# wifi.net
KiCad netlist of a schematic drawn in Altium Designer
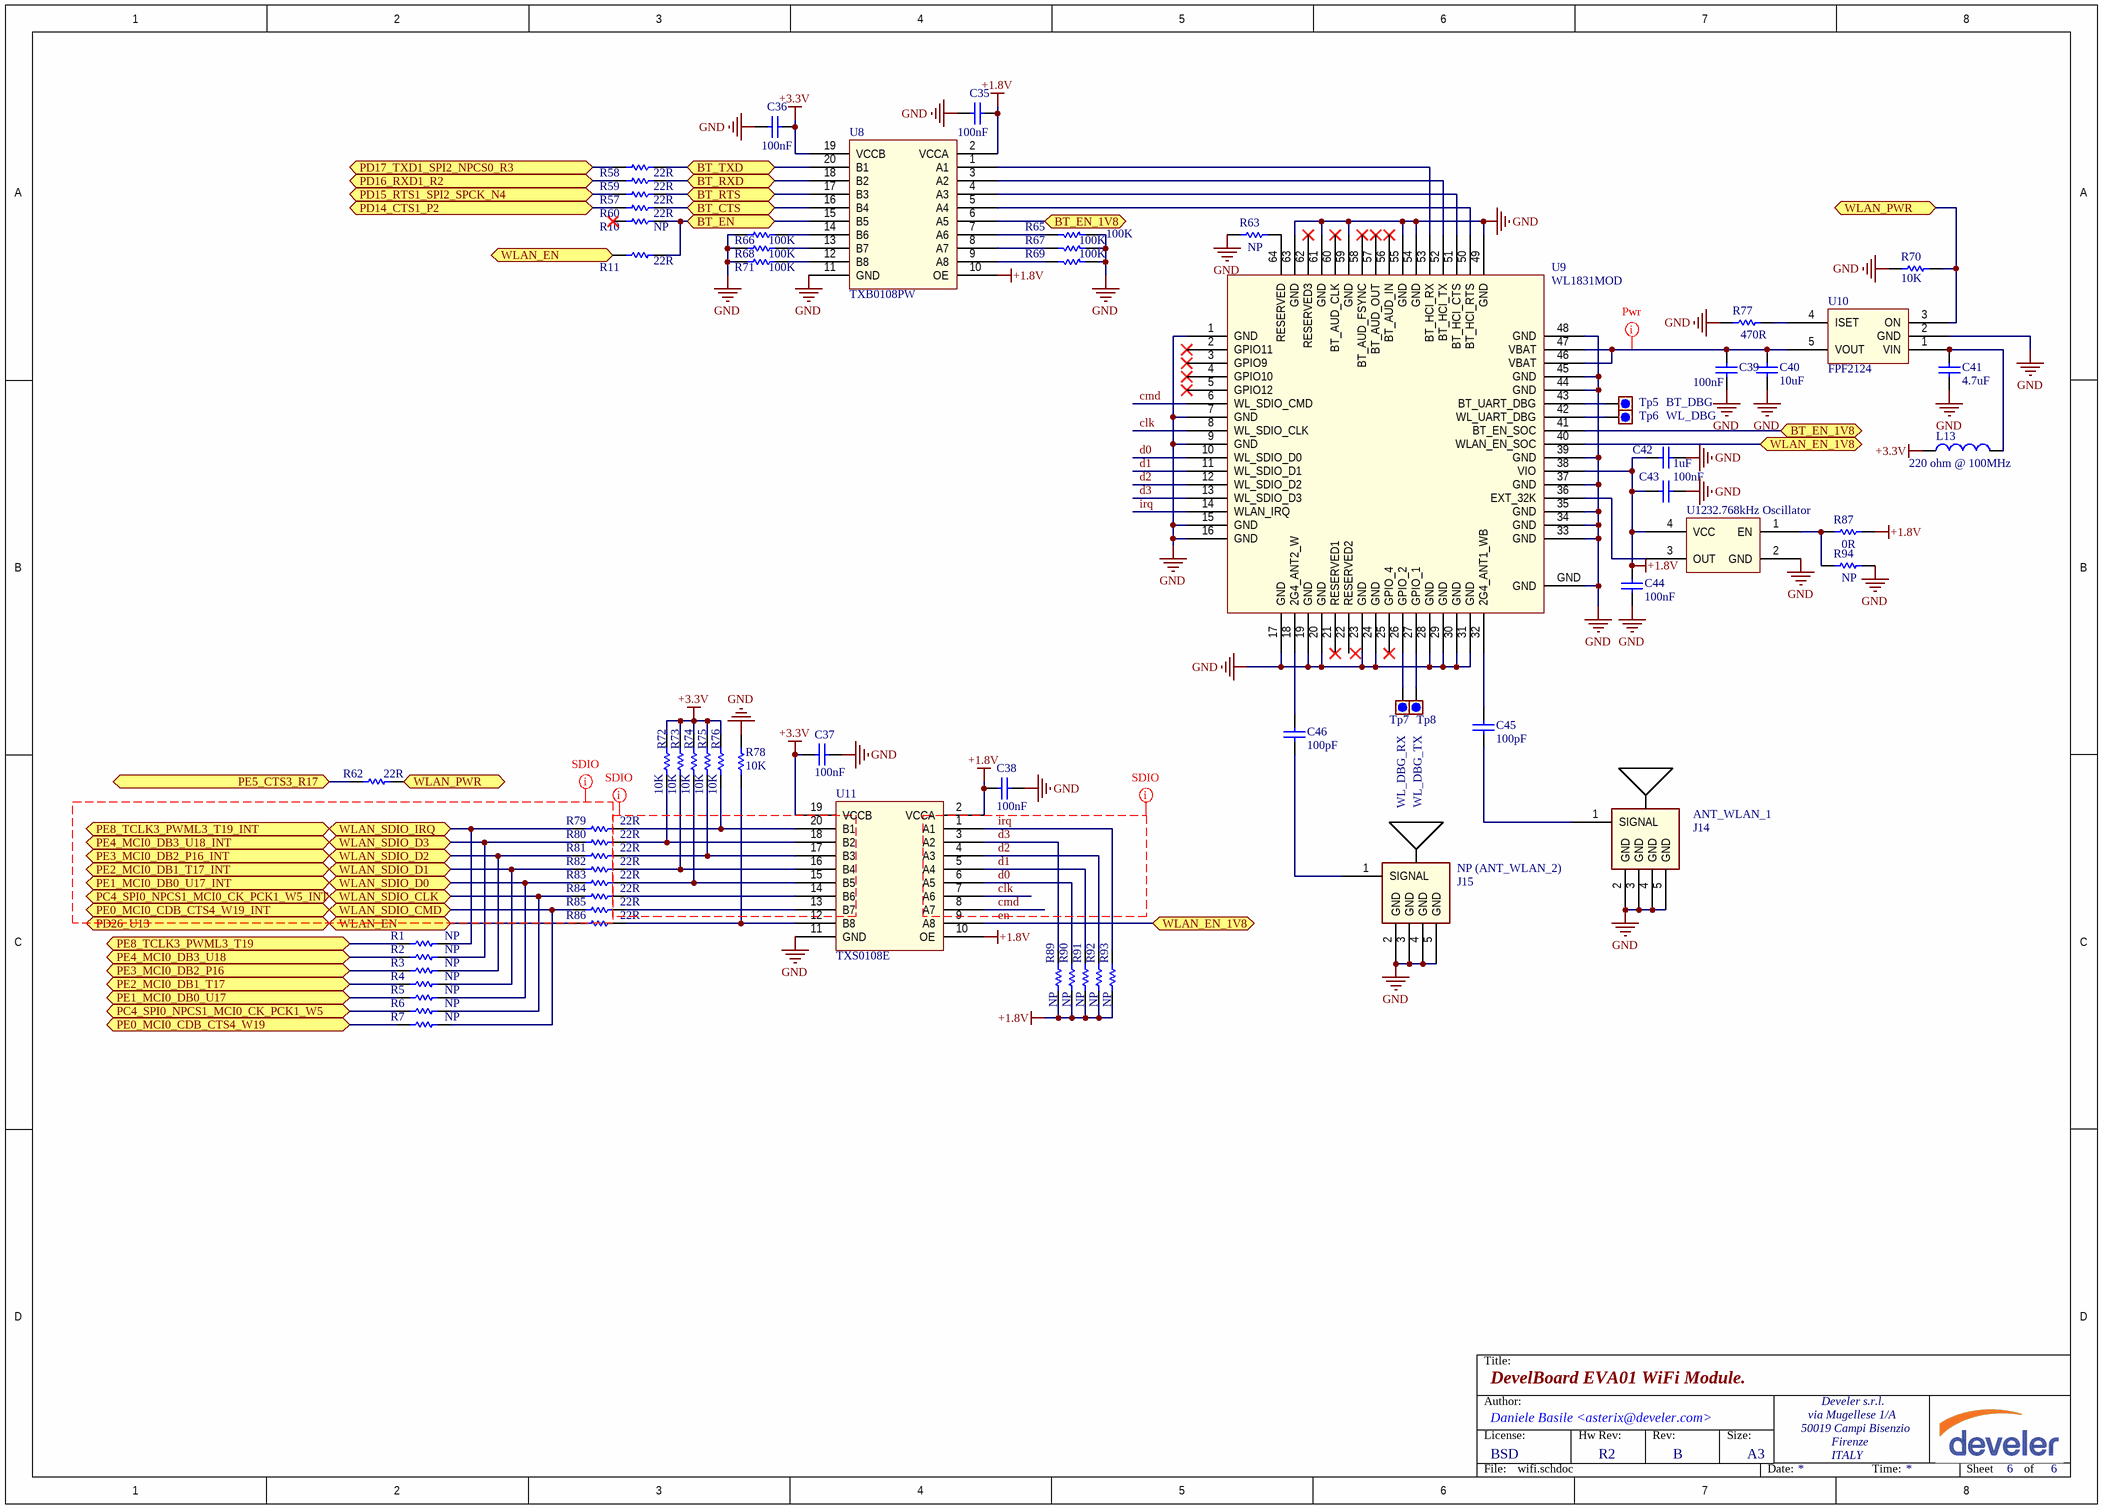
[diagram p0: wifi.schdoc]

(export (version "E")
  (design (tool "Eeschema 10.0.6"))
  (components
    (comp (ref "C35")
      (value "100nF")
      (footprint "0603_[1608]")
      (description "Ceramic X7R 50V")
      (fields (field (name "PUBLISHER") "Altium Limited"))
      (libsource (lib "DEVELER_Library") (part "Cap"))
    )
    (comp (ref "C36")
      (value "100nF")
      (footprint "0603_[1608]")
      (description "Ceramic X7R 50V")
      (fields (field (name "PUBLISHER") "Altium Limited"))
      (libsource (lib "DEVELER_Library") (part "Cap"))
    )
    (comp (ref "C37")
      (value "100nF")
      (footprint "0603_[1608]")
      (description "Ceramic X7R 50V")
      (fields (field (name "PUBLISHER") "Altium Limited"))
      (libsource (lib "DEVELER_Library") (part "Cap"))
    )
    (comp (ref "C38")
      (value "100nF")
      (footprint "0603_[1608]")
      (description "Ceramic X7R 50V")
      (fields (field (name "PUBLISHER") "Altium Limited"))
      (libsource (lib "DEVELER_Library") (part "Cap"))
    )
    (comp (ref "C39")
      (value "100nF")
      (footprint "0603_[1608]")
      (description "Ceramic X7R 50V")
      (fields (field (name "PUBLISHER") "Altium Limited"))
      (libsource (lib "DEVELER_Library") (part "Cap"))
    )
    (comp (ref "C40")
      (value "10uF")
      (footprint "1206_[3216]")
      (description "Ceramic X5R 25V")
      (fields (field (name "PUBLISHER") "Altium Limited"))
      (libsource (lib "DEVELER_Library") (part "Cap"))
    )
    (comp (ref "C41")
      (value "4.7uF")
      (footprint "0805_[2012]")
      (description "Ceramic X7R 10V")
      (fields (field (name "PUBLISHER") "Altium Limited"))
      (libsource (lib "DEVELER_Library") (part "Cap"))
    )
    (comp (ref "C42")
      (value "1uF")
      (footprint "1206_[3216]")
      (description "Ceramic X7R 50V")
      (fields (field (name "PUBLISHER") "Altium Limited"))
      (libsource (lib "DEVELER_Library") (part "Cap"))
    )
    (comp (ref "C43")
      (value "100nF")
      (footprint "0603_[1608]")
      (description "Ceramic X7R 50V")
      (fields (field (name "PUBLISHER") "Altium Limited"))
      (libsource (lib "DEVELER_Library") (part "Cap"))
    )
    (comp (ref "C44")
      (value "100nF")
      (footprint "0603_[1608]")
      (description "Ceramic X7R 50V")
      (fields (field (name "PUBLISHER") "Altium Limited"))
      (libsource (lib "DEVELER_Library") (part "Cap"))
    )
    (comp (ref "C45")
      (value "100pF")
      (footprint "0603_[1608]")
      (description "Ceramic COG 50V")
      (fields (field (name "PUBLISHER") "Altium Limited"))
      (libsource (lib "DEVELER_Library") (part "Cap"))
    )
    (comp (ref "C46")
      (value "100pF")
      (footprint "0603_[1608]")
      (description "Ceramic COG 50V")
      (fields (field (name "PUBLISHER") "Altium Limited"))
      (libsource (lib "DEVELER_Library") (part "Cap"))
    )
    (comp (ref "J14")
      (value "ANT_WLAN_1")
      (footprint "SMA_Jack_Female_5.08mm_THD")
      (description "SMA, Jack, Right angle, PCB socket, 50ohm (TE 5-1814400-1)")
      (libsource (lib "DEVELER_Library") (part "ANTENNA"))
    )
    (comp (ref "J15")
      (value "NP (ANT_WLAN_2)")
      (footprint "SMA_Jack_Female_5.08mm_THD")
      (description "SMA, Jack, Right angle, PCB socket, 50ohm (TE 5-1814400-1)")
      (libsource (lib "DEVELER_Library") (part "ANTENNA"))
    )
    (comp (ref "L13")
      (value "220 ohm @ 100MHz")
      (footprint "0805_[2012]")
      (description "Ferrite Beat (WE 742792022)")
      (libsource (lib "DEVELER_Library") (part "Inductor"))
    )
    (comp (ref "R1")
      (value "NP")
      (footprint "0603_[1608]")
      (description "Resistor")
      (fields (field (name "PUBLISHER") "Altium Limited"))
      (libsource (lib "DEVELER_Library") (part "Res1"))
    )
    (comp (ref "R2")
      (value "NP")
      (footprint "0603_[1608]")
      (description "Resistor")
      (fields (field (name "PUBLISHER") "Altium Limited"))
      (libsource (lib "DEVELER_Library") (part "Res1"))
    )
    (comp (ref "R3")
      (value "NP")
      (footprint "0603_[1608]")
      (description "Resistor")
      (fields (field (name "PUBLISHER") "Altium Limited"))
      (libsource (lib "DEVELER_Library") (part "Res1"))
    )
    (comp (ref "R4")
      (value "NP")
      (footprint "0603_[1608]")
      (description "Resistor")
      (fields (field (name "PUBLISHER") "Altium Limited"))
      (libsource (lib "DEVELER_Library") (part "Res1"))
    )
    (comp (ref "R5")
      (value "NP")
      (footprint "0603_[1608]")
      (description "Resistor")
      (fields (field (name "PUBLISHER") "Altium Limited"))
      (libsource (lib "DEVELER_Library") (part "Res1"))
    )
    (comp (ref "R6")
      (value "NP")
      (footprint "0603_[1608]")
      (description "Resistor")
      (fields (field (name "PUBLISHER") "Altium Limited"))
      (libsource (lib "DEVELER_Library") (part "Res1"))
    )
    (comp (ref "R7")
      (value "NP")
      (footprint "0603_[1608]")
      (description "Resistor")
      (fields (field (name "PUBLISHER") "Altium Limited"))
      (libsource (lib "DEVELER_Library") (part "Res1"))
    )
    (comp (ref "R10")
      (value "NP")
      (footprint "0603_[1608]")
      (description "Resistor")
      (fields (field (name "PUBLISHER") "Altium Limited"))
      (libsource (lib "DEVELER_Library") (part "Res1"))
    )
    (comp (ref "R11")
      (value "22R")
      (footprint "0603_[1608]")
      (description "Resistor")
      (fields (field (name "PUBLISHER") "Altium Limited"))
      (libsource (lib "DEVELER_Library") (part "Res1"))
    )
    (comp (ref "R57")
      (value "22R")
      (footprint "0603_[1608]")
      (description "Resistor")
      (fields (field (name "PUBLISHER") "Altium Limited"))
      (libsource (lib "DEVELER_Library") (part "Res1"))
    )
    (comp (ref "R58")
      (value "22R")
      (footprint "0603_[1608]")
      (description "Resistor")
      (fields (field (name "PUBLISHER") "Altium Limited"))
      (libsource (lib "DEVELER_Library") (part "Res1"))
    )
    (comp (ref "R59")
      (value "22R")
      (footprint "0603_[1608]")
      (description "Resistor")
      (fields (field (name "PUBLISHER") "Altium Limited"))
      (libsource (lib "DEVELER_Library") (part "Res1"))
    )
    (comp (ref "R60")
      (value "22R")
      (footprint "0603_[1608]")
      (description "Resistor")
      (fields (field (name "PUBLISHER") "Altium Limited"))
      (libsource (lib "DEVELER_Library") (part "Res1"))
    )
    (comp (ref "R62")
      (value "22R")
      (footprint "0603_[1608]")
      (description "Resistor")
      (fields (field (name "PUBLISHER") "Altium Limited"))
      (libsource (lib "DEVELER_Library") (part "Res1"))
    )
    (comp (ref "R63")
      (value "NP")
      (footprint "0603_[1608]")
      (description "Resistor")
      (fields (field (name "PUBLISHER") "Altium Limited"))
      (libsource (lib "DEVELER_Library") (part "Res1"))
    )
    (comp (ref "R65")
      (value "100K")
      (footprint "0603_[1608]")
      (description "Resistor")
      (fields (field (name "PUBLISHER") "Altium Limited"))
      (libsource (lib "DEVELER_Library") (part "Res1"))
    )
    (comp (ref "R66")
      (value "100K")
      (footprint "0603_[1608]")
      (description "Resistor")
      (fields (field (name "PUBLISHER") "Altium Limited"))
      (libsource (lib "DEVELER_Library") (part "Res1"))
    )
    (comp (ref "R67")
      (value "100K")
      (footprint "0603_[1608]")
      (description "Resistor")
      (fields (field (name "PUBLISHER") "Altium Limited"))
      (libsource (lib "DEVELER_Library") (part "Res1"))
    )
    (comp (ref "R68")
      (value "100K")
      (footprint "0603_[1608]")
      (description "Resistor")
      (fields (field (name "PUBLISHER") "Altium Limited"))
      (libsource (lib "DEVELER_Library") (part "Res1"))
    )
    (comp (ref "R69")
      (value "100K")
      (footprint "0603_[1608]")
      (description "Resistor")
      (fields (field (name "PUBLISHER") "Altium Limited"))
      (libsource (lib "DEVELER_Library") (part "Res1"))
    )
    (comp (ref "R70")
      (value "10K")
      (footprint "0603_[1608]")
      (description "Resistor")
      (fields (field (name "PUBLISHER") "Altium Limited"))
      (libsource (lib "DEVELER_Library") (part "Res1"))
    )
    (comp (ref "R71")
      (value "100K")
      (footprint "0603_[1608]")
      (description "Resistor")
      (fields (field (name "PUBLISHER") "Altium Limited"))
      (libsource (lib "DEVELER_Library") (part "Res1"))
    )
    (comp (ref "R72")
      (value "10K")
      (footprint "0603_[1608]")
      (description "Resistor")
      (fields (field (name "PUBLISHER") "Altium Limited"))
      (libsource (lib "DEVELER_Library") (part "Res1"))
    )
    (comp (ref "R73")
      (value "10K")
      (footprint "0603_[1608]")
      (description "Resistor")
      (fields (field (name "PUBLISHER") "Altium Limited"))
      (libsource (lib "DEVELER_Library") (part "Res1"))
    )
    (comp (ref "R74")
      (value "10K")
      (footprint "0603_[1608]")
      (description "Resistor")
      (fields (field (name "PUBLISHER") "Altium Limited"))
      (libsource (lib "DEVELER_Library") (part "Res1"))
    )
    (comp (ref "R75")
      (value "10K")
      (footprint "0603_[1608]")
      (description "Resistor")
      (fields (field (name "PUBLISHER") "Altium Limited"))
      (libsource (lib "DEVELER_Library") (part "Res1"))
    )
    (comp (ref "R76")
      (value "10K")
      (footprint "0603_[1608]")
      (description "Resistor")
      (fields (field (name "PUBLISHER") "Altium Limited"))
      (libsource (lib "DEVELER_Library") (part "Res1"))
    )
    (comp (ref "R77")
      (value "470R")
      (footprint "0603_[1608]")
      (description "Resistor")
      (fields (field (name "PUBLISHER") "Altium Limited"))
      (libsource (lib "DEVELER_Library") (part "Res1"))
    )
    (comp (ref "R78")
      (value "10K")
      (footprint "0603_[1608]")
      (description "Resistor")
      (fields (field (name "PUBLISHER") "Altium Limited"))
      (libsource (lib "DEVELER_Library") (part "Res1"))
    )
    (comp (ref "R79")
      (value "22R")
      (footprint "0603_[1608]")
      (description "Resistor")
      (fields (field (name "PUBLISHER") "Altium Limited"))
      (libsource (lib "DEVELER_Library") (part "Res1"))
    )
    (comp (ref "R80")
      (value "22R")
      (footprint "0603_[1608]")
      (description "Resistor")
      (fields (field (name "PUBLISHER") "Altium Limited"))
      (libsource (lib "DEVELER_Library") (part "Res1"))
    )
    (comp (ref "R81")
      (value "22R")
      (footprint "0603_[1608]")
      (description "Resistor")
      (fields (field (name "PUBLISHER") "Altium Limited"))
      (libsource (lib "DEVELER_Library") (part "Res1"))
    )
    (comp (ref "R82")
      (value "22R")
      (footprint "0603_[1608]")
      (description "Resistor")
      (fields (field (name "PUBLISHER") "Altium Limited"))
      (libsource (lib "DEVELER_Library") (part "Res1"))
    )
    (comp (ref "R83")
      (value "22R")
      (footprint "0603_[1608]")
      (description "Resistor")
      (fields (field (name "PUBLISHER") "Altium Limited"))
      (libsource (lib "DEVELER_Library") (part "Res1"))
    )
    (comp (ref "R84")
      (value "22R")
      (footprint "0603_[1608]")
      (description "Resistor")
      (fields (field (name "PUBLISHER") "Altium Limited"))
      (libsource (lib "DEVELER_Library") (part "Res1"))
    )
    (comp (ref "R85")
      (value "22R")
      (footprint "0603_[1608]")
      (description "Resistor")
      (fields (field (name "PUBLISHER") "Altium Limited"))
      (libsource (lib "DEVELER_Library") (part "Res1"))
    )
    (comp (ref "R86")
      (value "22R")
      (footprint "0603_[1608]")
      (description "Resistor")
      (fields (field (name "PUBLISHER") "Altium Limited"))
      (libsource (lib "DEVELER_Library") (part "Res1"))
    )
    (comp (ref "R87")
      (value "0R")
      (footprint "0603_[1608]")
      (description "Resistor")
      (fields (field (name "PUBLISHER") "Altium Limited"))
      (libsource (lib "DEVELER_Library") (part "Res1"))
    )
    (comp (ref "R89")
      (value "NP")
      (footprint "0603_[1608]")
      (description "Resistor")
      (fields (field (name "PUBLISHER") "Altium Limited"))
      (libsource (lib "DEVELER_Library") (part "Res1"))
    )
    (comp (ref "R90")
      (value "NP")
      (footprint "0603_[1608]")
      (description "Resistor")
      (fields (field (name "PUBLISHER") "Altium Limited"))
      (libsource (lib "DEVELER_Library") (part "Res1"))
    )
    (comp (ref "R91")
      (value "NP")
      (footprint "0603_[1608]")
      (description "Resistor")
      (fields (field (name "PUBLISHER") "Altium Limited"))
      (libsource (lib "DEVELER_Library") (part "Res1"))
    )
    (comp (ref "R92")
      (value "NP")
      (footprint "0603_[1608]")
      (description "Resistor")
      (fields (field (name "PUBLISHER") "Altium Limited"))
      (libsource (lib "DEVELER_Library") (part "Res1"))
    )
    (comp (ref "R93")
      (value "NP")
      (footprint "0603_[1608]")
      (description "Resistor")
      (fields (field (name "PUBLISHER") "Altium Limited"))
      (libsource (lib "DEVELER_Library") (part "Res1"))
    )
    (comp (ref "R94")
      (value "NP")
      (footprint "0603_[1608]")
      (description "Resistor")
      (fields (field (name "PUBLISHER") "Altium Limited"))
      (libsource (lib "DEVELER_Library") (part "Res1"))
    )
    (comp (ref "Tp5")
      (value "BT_DBG")
      (footprint "TEST_POINT_SMD_D1MM")
      (description "Test point")
      (libsource (lib "DEVELER_Library") (part "Test_point"))
    )
    (comp (ref "Tp6")
      (value "WL_DBG")
      (footprint "TEST_POINT_SMD_D1MM")
      (description "Test point")
      (libsource (lib "DEVELER_Library") (part "Test_point"))
    )
    (comp (ref "Tp7")
      (value "WL_DBG_RX")
      (footprint "TEST_POINT_SMD_D1MM")
      (description "Test point")
      (libsource (lib "") (part "Test_point_1"))
    )
    (comp (ref "Tp8")
      (value "WL_DBG_TX")
      (footprint "TEST_POINT_SMD_D1MM")
      (description "Test point")
      (libsource (lib "") (part "Test_point_1"))
    )
    (comp (ref "U8")
      (value "TXB0108PW")
      (footprint "TSOP65P640X120-20L")
      (description "8-bit bidirectional level translator")
      (libsource (lib "DEVELER_Library") (part "TXB0108PW"))
    )
    (comp (ref "U9")
      (value "WL1831MOD")
      (footprint "WL18XX_E-13.4X13.3-N100_0.75")
      (description "Wifi & Bluethoot module")
      (libsource (lib "DEVELER_Library") (part "WL1831MOD"))
    )
    (comp (ref "U10")
      (value "FPF2124")
      (footprint "SOT-23-5")
      (description "Power Load Switch")
      (libsource (lib "DEVELER_Library") (part "FPF2124"))
    )
    (comp (ref "U11")
      (value "TXS0108E")
      (footprint "TSOP65P640X120-20L")
      (description "8-bit bidirectional level translator")
      (libsource (lib "DEVELER_Library") (part "TXB0108PW"))
    )
    (comp (ref "U12")
      (value "32.768kHz Oscillator")
      (footprint "CRYSTAL_3.2X1.5MM_4P_SMD")
      (description "32.768kHz Oscillator (EPSON  X1B0002110001 SG-3030CM)")
      (libsource (lib "DEVELER_Library") (part "Si501/2/3_32768Hz"))
    )
  )
  (nets
    (net (code "1") (name "+1.8V") (class "Default")
      (node (ref "C35") (pin "2") (pinfunction "2_2") (pintype "passive"))
      (node (ref "C38") (pin "2") (pinfunction "2_2") (pintype "passive"))
      (node (ref "C42") (pin "2") (pinfunction "2_2") (pintype "passive"))
      (node (ref "C43") (pin "2") (pinfunction "2_2") (pintype "passive"))
      (node (ref "C44") (pin "2") (pinfunction "2_2") (pintype "passive"))
      (node (ref "R87") (pin "1") (pinfunction "1_1") (pintype "passive"))
      (node (ref "R89") (pin "1") (pinfunction "1_1") (pintype "passive"))
      (node (ref "R90") (pin "1") (pinfunction "1_1") (pintype "passive"))
      (node (ref "R91") (pin "1") (pinfunction "1_1") (pintype "passive"))
      (node (ref "R92") (pin "1") (pinfunction "1_1") (pintype "passive"))
      (node (ref "R93") (pin "1") (pinfunction "1_1") (pintype "passive"))
      (node (ref "U11") (pin "10") (pinfunction "OE_10") (pintype "passive"))
      (node (ref "U11") (pin "2") (pinfunction "VCCA_2") (pintype "passive"))
      (node (ref "U12") (pin "4") (pinfunction "VCC_4") (pintype "passive"))
      (node (ref "U8") (pin "10") (pinfunction "OE_10") (pintype "passive"))
      (node (ref "U8") (pin "2") (pinfunction "VCCA_2") (pintype "passive"))
      (node (ref "U9") (pin "38") (pinfunction "VIO_38") (pintype "passive"))
    )
    (net (code "2") (name "+3.3V") (class "Default")
      (node (ref "C36") (pin "2") (pinfunction "2_2") (pintype "passive"))
      (node (ref "C37") (pin "2") (pinfunction "2_2") (pintype "passive"))
      (node (ref "L13") (pin "2") (pinfunction "2_2") (pintype "passive"))
      (node (ref "R72") (pin "1") (pinfunction "1_1") (pintype "passive"))
      (node (ref "R73") (pin "1") (pinfunction "1_1") (pintype "passive"))
      (node (ref "R74") (pin "1") (pinfunction "1_1") (pintype "passive"))
      (node (ref "R75") (pin "1") (pinfunction "1_1") (pintype "passive"))
      (node (ref "R76") (pin "1") (pinfunction "1_1") (pintype "passive"))
      (node (ref "U11") (pin "19") (pinfunction "VCCB_19") (pintype "passive"))
      (node (ref "U8") (pin "19") (pinfunction "VCCB_19") (pintype "passive"))
    )
    (net (code "3") (name "/BT_CTS") (class "Default")
      (node (ref "R60") (pin "2") (pinfunction "2_2") (pintype "passive"))
      (node (ref "U8") (pin "16") (pinfunction "B4_16") (pintype "passive"))
    )
    (net (code "4") (name "/BT_EN") (class "Default")
      (node (ref "R10") (pin "2") (pinfunction "2_2") (pintype "passive"))
      (node (ref "R11") (pin "2") (pinfunction "2_2") (pintype "passive"))
      (node (ref "U8") (pin "15") (pinfunction "B5_15") (pintype "passive"))
    )
    (net (code "5") (name "/BT_EN_1V8") (class "Default")
      (node (ref "U8") (pin "6") (pinfunction "A5_6") (pintype "passive"))
      (node (ref "U9") (pin "41") (pinfunction "BT_EN_SOC_41") (pintype "passive"))
    )
    (net (code "6") (name "/BT_RTS") (class "Default")
      (node (ref "R57") (pin "2") (pinfunction "2_2") (pintype "passive"))
      (node (ref "U8") (pin "17") (pinfunction "B3_17") (pintype "passive"))
    )
    (net (code "7") (name "/BT_RXD") (class "Default")
      (node (ref "R59") (pin "2") (pinfunction "2_2") (pintype "passive"))
      (node (ref "U8") (pin "18") (pinfunction "B2_18") (pintype "passive"))
    )
    (net (code "8") (name "/BT_TXD") (class "Default")
      (node (ref "R58") (pin "2") (pinfunction "2_2") (pintype "passive"))
      (node (ref "U8") (pin "20") (pinfunction "B1_20") (pintype "passive"))
    )
    (net (code "9") (name "/PC4_SPI0_NPCS1_MCI0_CK_PCK1_W5") (class "Default")
      (node (ref "R6") (pin "2") (pinfunction "2_2") (pintype "passive"))
    )
    (net (code "11") (name "/PD14_CTS1_P2") (class "Default")
      (node (ref "R60") (pin "1") (pinfunction "1_1") (pintype "passive"))
    )
    (net (code "12") (name "/PD15_RTS1_SPI2_SPCK_N4") (class "Default")
      (node (ref "R57") (pin "1") (pinfunction "1_1") (pintype "passive"))
    )
    (net (code "13") (name "/PD16_RXD1_R2") (class "Default")
      (node (ref "R59") (pin "1") (pinfunction "1_1") (pintype "passive"))
    )
    (net (code "14") (name "/PD17_TXD1_SPI2_NPCS0_R3") (class "Default")
      (node (ref "R58") (pin "1") (pinfunction "1_1") (pintype "passive"))
    )
    (net (code "16") (name "/PE0_MCI0_CDB_CTS4_W19") (class "Default")
      (node (ref "R7") (pin "2") (pinfunction "2_2") (pintype "passive"))
    )
    (net (code "18") (name "/PE1_MCI0_DB0_U17") (class "Default")
      (node (ref "R5") (pin "2") (pinfunction "2_2") (pintype "passive"))
    )
    (net (code "20") (name "/PE2_MCI0_DB1_T17") (class "Default")
      (node (ref "R4") (pin "2") (pinfunction "2_2") (pintype "passive"))
    )
    (net (code "22") (name "/PE3_MCI0_DB2_P16") (class "Default")
      (node (ref "R3") (pin "2") (pinfunction "2_2") (pintype "passive"))
    )
    (net (code "24") (name "/PE4_MCI0_DB3_U18") (class "Default")
      (node (ref "R2") (pin "2") (pinfunction "2_2") (pintype "passive"))
    )
    (net (code "26") (name "/PE5_CTS3_R17") (class "Default")
      (node (ref "R62") (pin "1") (pinfunction "1_1") (pintype "passive"))
    )
    (net (code "27") (name "/PE8_TCLK3_PWML3_T19") (class "Default")
      (node (ref "R1") (pin "2") (pinfunction "2_2") (pintype "passive"))
    )
    (net (code "29") (name "/WLAN_EN") (class "Default")
      (node (ref "R11") (pin "1") (pinfunction "1_1") (pintype "passive"))
      (node (ref "R86") (pin "2") (pinfunction "2_2") (pintype "passive"))
    )
    (net (code "30") (name "/WLAN_PWR") (class "Default")
      (node (ref "R62") (pin "2") (pinfunction "2_2") (pintype "passive"))
      (node (ref "R70") (pin "2") (pinfunction "2_2") (pintype "passive"))
      (node (ref "U10") (pin "3") (pinfunction "ON_3") (pintype "passive"))
    )
    (net (code "31") (name "/WLAN_SDIO_CLK") (class "Default")
      (node (ref "R6") (pin "1") (pinfunction "1_1") (pintype "passive"))
      (node (ref "R84") (pin "2") (pinfunction "2_2") (pintype "passive"))
    )
    (net (code "32") (name "/WLAN_SDIO_CMD") (class "Default")
      (node (ref "R7") (pin "1") (pinfunction "1_1") (pintype "passive"))
      (node (ref "R85") (pin "2") (pinfunction "2_2") (pintype "passive"))
    )
    (net (code "33") (name "/WLAN_SDIO_D0") (class "Default")
      (node (ref "R5") (pin "1") (pinfunction "1_1") (pintype "passive"))
      (node (ref "R83") (pin "2") (pinfunction "2_2") (pintype "passive"))
    )
    (net (code "34") (name "/WLAN_SDIO_D1") (class "Default")
      (node (ref "R4") (pin "1") (pinfunction "1_1") (pintype "passive"))
      (node (ref "R82") (pin "2") (pinfunction "2_2") (pintype "passive"))
    )
    (net (code "35") (name "/WLAN_SDIO_D2") (class "Default")
      (node (ref "R3") (pin "1") (pinfunction "1_1") (pintype "passive"))
      (node (ref "R81") (pin "2") (pinfunction "2_2") (pintype "passive"))
    )
    (net (code "36") (name "/WLAN_SDIO_D3") (class "Default")
      (node (ref "R2") (pin "1") (pinfunction "1_1") (pintype "passive"))
      (node (ref "R80") (pin "2") (pinfunction "2_2") (pintype "passive"))
    )
    (net (code "37") (name "/WLAN_SDIO_IRQ") (class "Default")
      (node (ref "R1") (pin "1") (pinfunction "1_1") (pintype "passive"))
      (node (ref "R79") (pin "2") (pinfunction "2_2") (pintype "passive"))
    )
    (net (code "38") (name "/clk") (class "Default")
      (node (ref "U11") (pin "7") (pinfunction "A6_7") (pintype "passive"))
      (node (ref "U9") (pin "8") (pinfunction "WL_SDIO_CLK_8") (pintype "passive"))
    )
    (net (code "39") (name "/cmd") (class "Default")
      (node (ref "U11") (pin "8") (pinfunction "A7_8") (pintype "passive"))
      (node (ref "U9") (pin "6") (pinfunction "WL_SDIO_CMD_6") (pintype "passive"))
    )
    (net (code "40") (name "/d0") (class "Default")
      (node (ref "R90") (pin "2") (pinfunction "2_2") (pintype "passive"))
      (node (ref "U11") (pin "6") (pinfunction "A5_6") (pintype "passive"))
      (node (ref "U9") (pin "10") (pinfunction "WL_SDIO_D0_10") (pintype "passive"))
    )
    (net (code "41") (name "/d1") (class "Default")
      (node (ref "R91") (pin "2") (pinfunction "2_2") (pintype "passive"))
      (node (ref "U11") (pin "5") (pinfunction "A4_5") (pintype "passive"))
      (node (ref "U9") (pin "11") (pinfunction "WL_SDIO_D1_11") (pintype "passive"))
    )
    (net (code "42") (name "/d2") (class "Default")
      (node (ref "R92") (pin "2") (pinfunction "2_2") (pintype "passive"))
      (node (ref "U11") (pin "4") (pinfunction "A3_4") (pintype "passive"))
      (node (ref "U9") (pin "12") (pinfunction "WL_SDIO_D2_12") (pintype "passive"))
    )
    (net (code "43") (name "/d3") (class "Default")
      (node (ref "R89") (pin "2") (pinfunction "2_2") (pintype "passive"))
      (node (ref "U11") (pin "3") (pinfunction "A2_3") (pintype "passive"))
      (node (ref "U9") (pin "13") (pinfunction "WL_SDIO_D3_13") (pintype "passive"))
    )
    (net (code "44") (name "/en") (class "Default")
      (node (ref "U11") (pin "9") (pinfunction "A8_9") (pintype "passive"))
      (node (ref "U9") (pin "40") (pinfunction "WLAN_EN_SOC_40") (pintype "passive"))
    )
    (net (code "45") (name "/irq") (class "Default")
      (node (ref "R93") (pin "2") (pinfunction "2_2") (pintype "passive"))
      (node (ref "U11") (pin "1") (pinfunction "A1_1") (pintype "passive"))
      (node (ref "U9") (pin "14") (pinfunction "WLAN_IRQ_14") (pintype "passive"))
    )
    (net (code "46") (name "GND") (class "Default")
      (node (ref "C35") (pin "1") (pinfunction "1_1") (pintype "passive"))
      (node (ref "C36") (pin "1") (pinfunction "1_1") (pintype "passive"))
      (node (ref "C37") (pin "1") (pinfunction "1_1") (pintype "passive"))
      (node (ref "C38") (pin "1") (pinfunction "1_1") (pintype "passive"))
      (node (ref "C39") (pin "1") (pinfunction "1_1") (pintype "passive"))
      (node (ref "C40") (pin "1") (pinfunction "1_1") (pintype "passive"))
      (node (ref "C41") (pin "1") (pinfunction "1_1") (pintype "passive"))
      (node (ref "C42") (pin "1") (pinfunction "1_1") (pintype "passive"))
      (node (ref "C43") (pin "1") (pinfunction "1_1") (pintype "passive"))
      (node (ref "C44") (pin "1") (pinfunction "1_1") (pintype "passive"))
      (node (ref "J14") (pin "2") (pinfunction "GND_2") (pintype "passive"))
      (node (ref "J14") (pin "3") (pinfunction "GND_3") (pintype "passive"))
      (node (ref "J14") (pin "4") (pinfunction "GND_4") (pintype "passive"))
      (node (ref "J14") (pin "5") (pinfunction "GND_5") (pintype "passive"))
      (node (ref "J15") (pin "2") (pinfunction "GND_2") (pintype "passive"))
      (node (ref "J15") (pin "3") (pinfunction "GND_3") (pintype "passive"))
      (node (ref "J15") (pin "4") (pinfunction "GND_4") (pintype "passive"))
      (node (ref "J15") (pin "5") (pinfunction "GND_5") (pintype "passive"))
      (node (ref "R63") (pin "2") (pinfunction "2_2") (pintype "passive"))
      (node (ref "R65") (pin "2") (pinfunction "2_2") (pintype "passive"))
      (node (ref "R66") (pin "2") (pinfunction "2_2") (pintype "passive"))
      (node (ref "R67") (pin "2") (pinfunction "2_2") (pintype "passive"))
      (node (ref "R68") (pin "2") (pinfunction "2_2") (pintype "passive"))
      (node (ref "R69") (pin "2") (pinfunction "2_2") (pintype "passive"))
      (node (ref "R70") (pin "1") (pinfunction "1_1") (pintype "passive"))
      (node (ref "R71") (pin "2") (pinfunction "2_2") (pintype "passive"))
      (node (ref "R77") (pin "2") (pinfunction "2_2") (pintype "passive"))
      (node (ref "R78") (pin "1") (pinfunction "1_1") (pintype "passive"))
      (node (ref "R94") (pin "1") (pinfunction "1_1") (pintype "passive"))
      (node (ref "U10") (pin "2") (pinfunction "GND_2") (pintype "passive"))
      (node (ref "U11") (pin "11") (pinfunction "GND_11") (pintype "passive"))
      (node (ref "U12") (pin "2") (pinfunction "GND_2") (pintype "passive"))
      (node (ref "U8") (pin "11") (pinfunction "GND_11") (pintype "passive"))
      (node (ref "U9") (pin "1") (pinfunction "GND_1") (pintype "passive"))
      (node (ref "U9") (pin "15") (pinfunction "GND_15") (pintype "passive"))
      (node (ref "U9") (pin "16") (pinfunction "GND_16") (pintype "passive"))
      (node (ref "U9") (pin "17") (pinfunction "GND_17") (pintype "passive"))
      (node (ref "U9") (pin "19") (pinfunction "GND_19") (pintype "passive"))
      (node (ref "U9") (pin "20") (pinfunction "GND_20") (pintype "passive"))
      (node (ref "U9") (pin "23") (pinfunction "GND_23") (pintype "passive"))
      (node (ref "U9") (pin "24") (pinfunction "GND_24") (pintype "passive"))
      (node (ref "U9") (pin "28") (pinfunction "GND_28") (pintype "passive"))
      (node (ref "U9") (pin "29") (pinfunction "GND_29") (pintype "passive"))
      (node (ref "U9") (pin "30") (pinfunction "GND_30") (pintype "passive"))
      (node (ref "U9") (pin "31") (pinfunction "GND_31") (pintype "passive"))
      (node (ref "U9") (pin "33") (pinfunction "GND_33") (pintype "passive"))
      (node (ref "U9") (pin "34") (pinfunction "GND_34") (pintype "passive"))
      (node (ref "U9") (pin "35") (pinfunction "GND_35") (pintype "passive"))
      (node (ref "U9") (pin "37") (pinfunction "GND_37") (pintype "passive"))
      (node (ref "U9") (pin "39") (pinfunction "GND_39") (pintype "passive"))
      (node (ref "U9") (pin "44") (pinfunction "GND_44") (pintype "passive"))
      (node (ref "U9") (pin "45") (pinfunction "GND_45") (pintype "passive"))
      (node (ref "U9") (pin "48") (pinfunction "GND_48") (pintype "passive"))
      (node (ref "U9") (pin "49") (pinfunction "GND_49") (pintype "passive"))
      (node (ref "U9") (pin "54") (pinfunction "GND_54") (pintype "passive"))
      (node (ref "U9") (pin "55") (pinfunction "GND_55") (pintype "passive"))
      (node (ref "U9") (pin "59") (pinfunction "GND_59") (pintype "passive"))
      (node (ref "U9") (pin "61") (pinfunction "GND_61") (pintype "passive"))
      (node (ref "U9") (pin "63") (pinfunction "GND_63") (pintype "passive"))
      (node (ref "U9") (pin "7") (pinfunction "GND_7") (pintype "passive"))
      (node (ref "U9") (pin "9") (pinfunction "GND_9") (pintype "passive"))
      (node (ref "U9") (pin "GND") (pinfunction "GND_GND") (pintype "passive"))
    )
    (net (code "47") (name "Net-(J14-SIGNAL)") (class "Default")
      (node (ref "C45") (pin "2") (pinfunction "2_2") (pintype "passive"))
      (node (ref "J14") (pin "1") (pinfunction "SIGNAL_1") (pintype "passive"))
    )
    (net (code "48") (name "Net-(J15-SIGNAL)") (class "Default")
      (node (ref "C46") (pin "2") (pinfunction "2_2") (pintype "passive"))
      (node (ref "J15") (pin "1") (pinfunction "SIGNAL_1") (pintype "passive"))
    )
    (net (code "49") (name "Net-(U8-A1)") (class "Default")
      (node (ref "U8") (pin "1") (pinfunction "A1_1") (pintype "passive"))
      (node (ref "U9") (pin "53") (pinfunction "BT_HCI_RX_53") (pintype "passive"))
    )
    (net (code "50") (name "Net-(U8-A2)") (class "Default")
      (node (ref "U8") (pin "3") (pinfunction "A2_3") (pintype "passive"))
      (node (ref "U9") (pin "52") (pinfunction "BT_HCI_TX_52") (pintype "passive"))
    )
    (net (code "51") (name "Net-(U8-A3)") (class "Default")
      (node (ref "U8") (pin "4") (pinfunction "A3_4") (pintype "passive"))
      (node (ref "U9") (pin "51") (pinfunction "BT_HCI_CTS_51") (pintype "passive"))
    )
    (net (code "52") (name "Net-(U8-A4)") (class "Default")
      (node (ref "U8") (pin "5") (pinfunction "A4_5") (pintype "passive"))
      (node (ref "U9") (pin "50") (pinfunction "BT_HCI_RTS_50") (pintype "passive"))
    )
    (net (code "53") (name "Net-(U8-A6)") (class "Default")
      (node (ref "R65") (pin "1") (pinfunction "1_1") (pintype "passive"))
      (node (ref "U8") (pin "7") (pinfunction "A6_7") (pintype "passive"))
    )
    (net (code "54") (name "Net-(U8-A7)") (class "Default")
      (node (ref "R67") (pin "1") (pinfunction "1_1") (pintype "passive"))
      (node (ref "U8") (pin "8") (pinfunction "A7_8") (pintype "passive"))
    )
    (net (code "55") (name "Net-(U8-A8)") (class "Default")
      (node (ref "R69") (pin "1") (pinfunction "1_1") (pintype "passive"))
      (node (ref "U8") (pin "9") (pinfunction "A8_9") (pintype "passive"))
    )
    (net (code "56") (name "Net-(U8-B6)") (class "Default")
      (node (ref "R66") (pin "1") (pinfunction "1_1") (pintype "passive"))
      (node (ref "U8") (pin "14") (pinfunction "B6_14") (pintype "passive"))
    )
    (net (code "57") (name "Net-(U8-B7)") (class "Default")
      (node (ref "R68") (pin "1") (pinfunction "1_1") (pintype "passive"))
      (node (ref "U8") (pin "13") (pinfunction "B7_13") (pintype "passive"))
    )
    (net (code "58") (name "Net-(U8-B8)") (class "Default")
      (node (ref "R71") (pin "1") (pinfunction "1_1") (pintype "passive"))
      (node (ref "U8") (pin "12") (pinfunction "B8_12") (pintype "passive"))
    )
    (net (code "59") (name "Net-(U9-2G4_ANT1_WB)") (class "Default")
      (node (ref "C45") (pin "1") (pinfunction "1_1") (pintype "passive"))
      (node (ref "U9") (pin "32") (pinfunction "2G4_ANT1_WB_32") (pintype "passive"))
    )
    (net (code "60") (name "Net-(U9-2G4_ANT2_W)") (class "Default")
      (node (ref "C46") (pin "1") (pinfunction "1_1") (pintype "passive"))
      (node (ref "U9") (pin "18") (pinfunction "2G4_ANT2_W_18") (pintype "passive"))
    )
    (net (code "61") (name "Net-(U9-BT_UART_DBG)") (class "Default")
      (node (ref "Tp5") (pin "1") (pinfunction "1_1") (pintype "passive"))
      (node (ref "U9") (pin "43") (pinfunction "BT_UART_DBG_43") (pintype "passive"))
    )
    (net (code "62") (name "Net-(U9-GPIO_1)") (class "Default")
      (node (ref "Tp8") (pin "1") (pinfunction "1_1") (pintype "passive"))
      (node (ref "U9") (pin "27") (pinfunction "GPIO_1_27") (pintype "passive"))
    )
    (net (code "63") (name "Net-(U9-GPIO_2)") (class "Default")
      (node (ref "Tp7") (pin "1") (pinfunction "1_1") (pintype "passive"))
      (node (ref "U9") (pin "26") (pinfunction "GPIO_2_26") (pintype "passive"))
    )
    (net (code "64") (name "Net-(U9-RESERVED)") (class "Default")
      (node (ref "R63") (pin "1") (pinfunction "1_1") (pintype "passive"))
      (node (ref "U9") (pin "64") (pinfunction "RESERVED_64") (pintype "passive"))
    )
    (net (code "65") (name "Net-(U9-WL_UART_DBG)") (class "Default")
      (node (ref "Tp6") (pin "1") (pinfunction "1_1") (pintype "passive"))
      (node (ref "U9") (pin "42") (pinfunction "WL_UART_DBG_42") (pintype "passive"))
    )
    (net (code "66") (name "Net-(U10-ISET)") (class "Default")
      (node (ref "R77") (pin "1") (pinfunction "1_1") (pintype "passive"))
      (node (ref "U10") (pin "4") (pinfunction "ISET_4") (pintype "passive"))
    )
    (net (code "67") (name "Net-(U10-VIN)") (class "Default")
      (node (ref "C41") (pin "2") (pinfunction "2_2") (pintype "passive"))
      (node (ref "L13") (pin "1") (pinfunction "1_1") (pintype "passive"))
      (node (ref "U10") (pin "1") (pinfunction "VIN_1") (pintype "passive"))
    )
    (net (code "68") (name "Net-(U10-VOUT)") (class "Default")
      (node (ref "C39") (pin "2") (pinfunction "2_2") (pintype "passive"))
      (node (ref "C40") (pin "2") (pinfunction "2_2") (pintype "passive"))
      (node (ref "U10") (pin "5") (pinfunction "VOUT_5") (pintype "passive"))
      (node (ref "U9") (pin "46") (pinfunction "VBAT_46") (pintype "passive"))
      (node (ref "U9") (pin "47") (pinfunction "VBAT_47") (pintype "passive"))
    )
    (net (code "69") (name "Net-(U11-B1)") (class "Default")
      (node (ref "R76") (pin "2") (pinfunction "2_2") (pintype "passive"))
      (node (ref "R79") (pin "1") (pinfunction "1_1") (pintype "passive"))
      (node (ref "U11") (pin "20") (pinfunction "B1_20") (pintype "passive"))
    )
    (net (code "70") (name "Net-(U11-B2)") (class "Default")
      (node (ref "R72") (pin "2") (pinfunction "2_2") (pintype "passive"))
      (node (ref "R80") (pin "1") (pinfunction "1_1") (pintype "passive"))
      (node (ref "U11") (pin "18") (pinfunction "B2_18") (pintype "passive"))
    )
    (net (code "71") (name "Net-(U11-B3)") (class "Default")
      (node (ref "R75") (pin "2") (pinfunction "2_2") (pintype "passive"))
      (node (ref "R81") (pin "1") (pinfunction "1_1") (pintype "passive"))
      (node (ref "U11") (pin "17") (pinfunction "B3_17") (pintype "passive"))
    )
    (net (code "72") (name "Net-(U11-B4)") (class "Default")
      (node (ref "R73") (pin "2") (pinfunction "2_2") (pintype "passive"))
      (node (ref "R82") (pin "1") (pinfunction "1_1") (pintype "passive"))
      (node (ref "U11") (pin "16") (pinfunction "B4_16") (pintype "passive"))
    )
    (net (code "73") (name "Net-(U11-B5)") (class "Default")
      (node (ref "R74") (pin "2") (pinfunction "2_2") (pintype "passive"))
      (node (ref "R83") (pin "1") (pinfunction "1_1") (pintype "passive"))
      (node (ref "U11") (pin "15") (pinfunction "B5_15") (pintype "passive"))
    )
    (net (code "74") (name "Net-(U11-B6)") (class "Default")
      (node (ref "R84") (pin "1") (pinfunction "1_1") (pintype "passive"))
      (node (ref "U11") (pin "14") (pinfunction "B6_14") (pintype "passive"))
    )
    (net (code "75") (name "Net-(U11-B7)") (class "Default")
      (node (ref "R85") (pin "1") (pinfunction "1_1") (pintype "passive"))
      (node (ref "U11") (pin "13") (pinfunction "B7_13") (pintype "passive"))
    )
    (net (code "76") (name "Net-(U11-B8)") (class "Default")
      (node (ref "R78") (pin "2") (pinfunction "2_2") (pintype "passive"))
      (node (ref "R86") (pin "1") (pinfunction "1_1") (pintype "passive"))
      (node (ref "U11") (pin "12") (pinfunction "B8_12") (pintype "passive"))
    )
    (net (code "77") (name "Net-(U12-EN)") (class "Default")
      (node (ref "R87") (pin "2") (pinfunction "2_2") (pintype "passive"))
      (node (ref "R94") (pin "2") (pinfunction "2_2") (pintype "passive"))
      (node (ref "U12") (pin "1") (pinfunction "EN_1") (pintype "passive"))
    )
    (net (code "78") (name "Net-(U12-OUT)") (class "Default")
      (node (ref "U12") (pin "3") (pinfunction "OUT_3") (pintype "passive"))
      (node (ref "U9") (pin "36") (pinfunction "EXT_32K_36") (pintype "passive"))
    )
    (net (code "79") (name "unconnected-(R10-Pad1)") (class "Default")
      (node (ref "R10") (pin "1") (pinfunction "1_1") (pintype "passive+no_connect"))
    )
    (net (code "80") (name "unconnected-(U9-BT_AUD_CLK-Pad60)") (class "Default")
      (node (ref "U9") (pin "60") (pinfunction "BT_AUD_CLK_60") (pintype "passive+no_connect"))
    )
    (net (code "81") (name "unconnected-(U9-BT_AUD_FSYNC-Pad58)") (class "Default")
      (node (ref "U9") (pin "58") (pinfunction "BT_AUD_FSYNC_58") (pintype "passive+no_connect"))
    )
    (net (code "82") (name "unconnected-(U9-BT_AUD_IN-Pad56)") (class "Default")
      (node (ref "U9") (pin "56") (pinfunction "BT_AUD_IN_56") (pintype "passive+no_connect"))
    )
    (net (code "83") (name "unconnected-(U9-BT_AUD_OUT-Pad57)") (class "Default")
      (node (ref "U9") (pin "57") (pinfunction "BT_AUD_OUT_57") (pintype "passive+no_connect"))
    )
    (net (code "84") (name "unconnected-(U9-GPIO9-Pad3)") (class "Default")
      (node (ref "U9") (pin "3") (pinfunction "GPIO9_3") (pintype "passive+no_connect"))
    )
    (net (code "85") (name "unconnected-(U9-GPIO10-Pad4)") (class "Default")
      (node (ref "U9") (pin "4") (pinfunction "GPIO10_4") (pintype "passive+no_connect"))
    )
    (net (code "86") (name "unconnected-(U9-GPIO11-Pad2)") (class "Default")
      (node (ref "U9") (pin "2") (pinfunction "GPIO11_2") (pintype "passive+no_connect"))
    )
    (net (code "87") (name "unconnected-(U9-GPIO12-Pad5)") (class "Default")
      (node (ref "U9") (pin "5") (pinfunction "GPIO12_5") (pintype "passive+no_connect"))
    )
    (net (code "88") (name "unconnected-(U9-GPIO_4-Pad25)") (class "Default")
      (node (ref "U9") (pin "25") (pinfunction "GPIO_4_25") (pintype "passive+no_connect"))
    )
    (net (code "89") (name "unconnected-(U9-RESERVED1-Pad21)") (class "Default")
      (node (ref "U9") (pin "21") (pinfunction "RESERVED1_21") (pintype "passive+no_connect"))
    )
    (net (code "90") (name "unconnected-(U9-RESERVED2-Pad22)") (class "Default")
      (node (ref "U9") (pin "22") (pinfunction "RESERVED2_22") (pintype "passive"))
    )
    (net (code "91") (name "unconnected-(U9-RESERVED3-Pad62)") (class "Default")
      (node (ref "U9") (pin "62") (pinfunction "RESERVED3_62") (pintype "passive+no_connect"))
    )
  )
)
